# O4MEGA.net
KiCad netlist of a schematic drawn in EAGLE
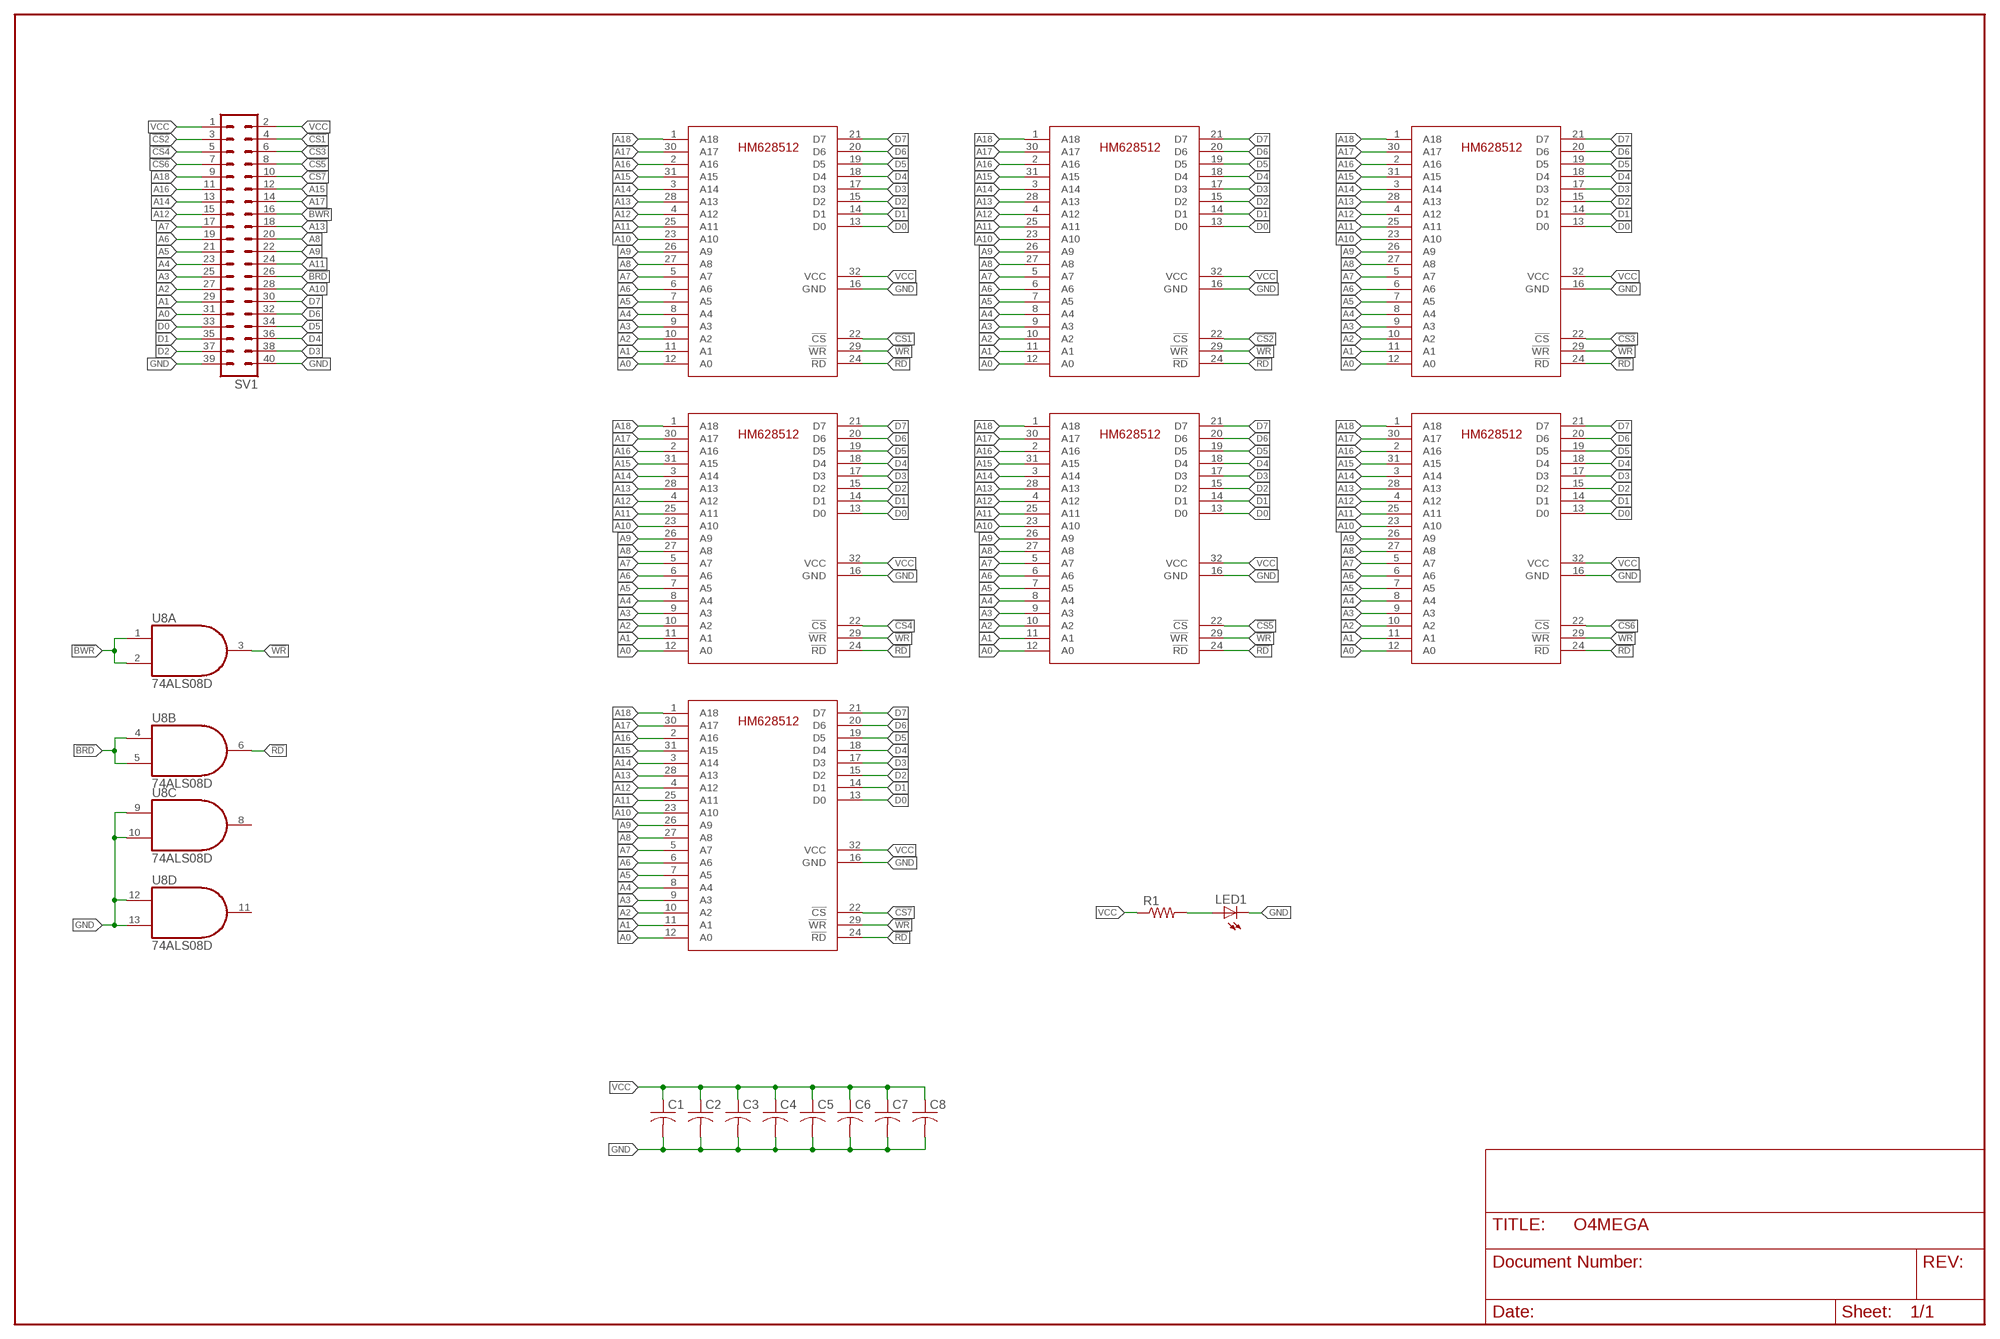
[diagram p0: schematic, sheet 1]

(export (version "E")
  (design (tool "Eeschema 10.0.6"))
  (components
    (comp (ref "C1")
      (value "C-USC0805K")
      (footprint "eagle-import:C0805K")
      (libsource (lib "eagle-import") (part "C-USC0805K"))
    )
    (comp (ref "C2")
      (value "C-USC0805K")
      (footprint "eagle-import:C0805K")
      (libsource (lib "eagle-import") (part "C-USC0805K"))
    )
    (comp (ref "C3")
      (value "C-USC0805K")
      (footprint "eagle-import:C0805K")
      (libsource (lib "eagle-import") (part "C-USC0805K"))
    )
    (comp (ref "C4")
      (value "C-USC0805K")
      (footprint "eagle-import:C0805K")
      (libsource (lib "eagle-import") (part "C-USC0805K"))
    )
    (comp (ref "C5")
      (value "C-USC0805K")
      (footprint "eagle-import:C0805K")
      (libsource (lib "eagle-import") (part "C-USC0805K"))
    )
    (comp (ref "C6")
      (value "C-USC0805K")
      (footprint "eagle-import:C0805K")
      (libsource (lib "eagle-import") (part "C-USC0805K"))
    )
    (comp (ref "C7")
      (value "C-USC0805K")
      (footprint "eagle-import:C0805K")
      (libsource (lib "eagle-import") (part "C-USC0805K"))
    )
    (comp (ref "C8")
      (value "C-USC0805K")
      (footprint "eagle-import:C0805K")
      (libsource (lib "eagle-import") (part "C-USC0805K"))
    )
    (comp (ref "LED1")
      (value "LEDCHIP-LED0805")
      (footprint "eagle-import:CHIP-LED0805")
      (libsource (lib "eagle-import") (part "LEDCHIP-LED0805"))
    )
    (comp (ref "R1")
      (value "R-US_M0805")
      (footprint "eagle-import:M0805")
      (libsource (lib "eagle-import") (part "R-US_M0805"))
    )
    (comp (ref "SV1")
      (value "MA20-2")
      (footprint "eagle-import:MA20-2")
      (libsource (lib "eagle-import") (part "MA20-2"))
    )
    (comp (ref "U1")
      (value "HM628512")
      (footprint "eagle-import:SOP32L")
      (libsource (lib "eagle-import") (part "HM628512"))
    )
    (comp (ref "U2")
      (value "HM628512")
      (footprint "eagle-import:SOP32L")
      (libsource (lib "eagle-import") (part "HM628512"))
    )
    (comp (ref "U3")
      (value "HM628512")
      (footprint "eagle-import:SOP32L")
      (libsource (lib "eagle-import") (part "HM628512"))
    )
    (comp (ref "U4")
      (value "HM628512")
      (footprint "eagle-import:SOP32L")
      (libsource (lib "eagle-import") (part "HM628512"))
    )
    (comp (ref "U5")
      (value "HM628512")
      (footprint "eagle-import:SOP32L")
      (libsource (lib "eagle-import") (part "HM628512"))
    )
    (comp (ref "U6")
      (value "HM628512")
      (footprint "eagle-import:SOP32L")
      (libsource (lib "eagle-import") (part "HM628512"))
    )
    (comp (ref "U7")
      (value "HM628512")
      (footprint "eagle-import:SOP32L")
      (libsource (lib "eagle-import") (part "HM628512"))
    )
    (comp (ref "U8")
      (value "74ALS08D")
      (footprint "eagle-import:SO14")
      (libsource (lib "eagle-import") (part "7408DALS"))
    )
  )
  (nets
    (net (code "1") (name "/~{BRD}") (class "Default")
      (node (ref "SV1") (pin "26") (pinfunction "26_26") (pintype "passive"))
      (node (ref "U8") (pin "4") (pinfunction "I0_4") (pintype "input"))
      (node (ref "U8") (pin "5") (pinfunction "I1_5") (pintype "input"))
    )
    (net (code "2") (name "/~{BWR}") (class "Default")
      (node (ref "SV1") (pin "16") (pinfunction "16_16") (pintype "passive"))
      (node (ref "U8") (pin "1") (pinfunction "I0_1") (pintype "input"))
      (node (ref "U8") (pin "2") (pinfunction "I1_2") (pintype "input"))
    )
    (net (code "3") (name "/~{CS1}") (class "Default")
      (node (ref "SV1") (pin "4") (pinfunction "4_4") (pintype "passive"))
      (node (ref "U1") (pin "22") (pinfunction "~{CS}_22") (pintype "bidirectional"))
    )
    (net (code "4") (name "/~{CS2}") (class "Default")
      (node (ref "SV1") (pin "3") (pinfunction "3_3") (pintype "passive"))
      (node (ref "U2") (pin "22") (pinfunction "~{CS}_22") (pintype "bidirectional"))
    )
    (net (code "5") (name "/~{CS3}") (class "Default")
      (node (ref "SV1") (pin "6") (pinfunction "6_6") (pintype "passive"))
      (node (ref "U3") (pin "22") (pinfunction "~{CS}_22") (pintype "bidirectional"))
    )
    (net (code "6") (name "/~{CS4}") (class "Default")
      (node (ref "SV1") (pin "5") (pinfunction "5_5") (pintype "passive"))
      (node (ref "U4") (pin "22") (pinfunction "~{CS}_22") (pintype "bidirectional"))
    )
    (net (code "7") (name "/~{CS5}") (class "Default")
      (node (ref "SV1") (pin "8") (pinfunction "8_8") (pintype "passive"))
      (node (ref "U5") (pin "22") (pinfunction "~{CS}_22") (pintype "bidirectional"))
    )
    (net (code "8") (name "/~{CS6}") (class "Default")
      (node (ref "SV1") (pin "7") (pinfunction "7_7") (pintype "passive"))
      (node (ref "U6") (pin "22") (pinfunction "~{CS}_22") (pintype "bidirectional"))
    )
    (net (code "9") (name "/~{CS7}") (class "Default")
      (node (ref "SV1") (pin "10") (pinfunction "10_10") (pintype "passive"))
      (node (ref "U7") (pin "22") (pinfunction "~{CS}_22") (pintype "bidirectional"))
    )
    (net (code "10") (name "/~{RD}") (class "Default")
      (node (ref "U1") (pin "24") (pinfunction "~{RD}_24") (pintype "bidirectional"))
      (node (ref "U2") (pin "24") (pinfunction "~{RD}_24") (pintype "bidirectional"))
      (node (ref "U3") (pin "24") (pinfunction "~{RD}_24") (pintype "bidirectional"))
      (node (ref "U4") (pin "24") (pinfunction "~{RD}_24") (pintype "bidirectional"))
      (node (ref "U5") (pin "24") (pinfunction "~{RD}_24") (pintype "bidirectional"))
      (node (ref "U6") (pin "24") (pinfunction "~{RD}_24") (pintype "bidirectional"))
      (node (ref "U7") (pin "24") (pinfunction "~{RD}_24") (pintype "bidirectional"))
      (node (ref "U8") (pin "6") (pinfunction "O_6") (pintype "output"))
    )
    (net (code "11") (name "/~{WR}") (class "Default")
      (node (ref "U1") (pin "29") (pinfunction "~{WR}_29") (pintype "bidirectional"))
      (node (ref "U2") (pin "29") (pinfunction "~{WR}_29") (pintype "bidirectional"))
      (node (ref "U3") (pin "29") (pinfunction "~{WR}_29") (pintype "bidirectional"))
      (node (ref "U4") (pin "29") (pinfunction "~{WR}_29") (pintype "bidirectional"))
      (node (ref "U5") (pin "29") (pinfunction "~{WR}_29") (pintype "bidirectional"))
      (node (ref "U6") (pin "29") (pinfunction "~{WR}_29") (pintype "bidirectional"))
      (node (ref "U7") (pin "29") (pinfunction "~{WR}_29") (pintype "bidirectional"))
      (node (ref "U8") (pin "3") (pinfunction "O_3") (pintype "output"))
    )
    (net (code "12") (name "A0") (class "Default")
      (node (ref "SV1") (pin "31") (pinfunction "31_31") (pintype "passive"))
      (node (ref "U1") (pin "12") (pinfunction "A0_12") (pintype "input"))
      (node (ref "U2") (pin "12") (pinfunction "A0_12") (pintype "input"))
      (node (ref "U3") (pin "12") (pinfunction "A0_12") (pintype "input"))
      (node (ref "U4") (pin "12") (pinfunction "A0_12") (pintype "input"))
      (node (ref "U5") (pin "12") (pinfunction "A0_12") (pintype "input"))
      (node (ref "U6") (pin "12") (pinfunction "A0_12") (pintype "input"))
      (node (ref "U7") (pin "12") (pinfunction "A0_12") (pintype "input"))
    )
    (net (code "13") (name "A1") (class "Default")
      (node (ref "SV1") (pin "29") (pinfunction "29_29") (pintype "passive"))
      (node (ref "U1") (pin "11") (pinfunction "A1_11") (pintype "input"))
      (node (ref "U2") (pin "11") (pinfunction "A1_11") (pintype "input"))
      (node (ref "U3") (pin "11") (pinfunction "A1_11") (pintype "input"))
      (node (ref "U4") (pin "11") (pinfunction "A1_11") (pintype "input"))
      (node (ref "U5") (pin "11") (pinfunction "A1_11") (pintype "input"))
      (node (ref "U6") (pin "11") (pinfunction "A1_11") (pintype "input"))
      (node (ref "U7") (pin "11") (pinfunction "A1_11") (pintype "input"))
    )
    (net (code "14") (name "A2") (class "Default")
      (node (ref "SV1") (pin "27") (pinfunction "27_27") (pintype "passive"))
      (node (ref "U1") (pin "10") (pinfunction "A2_10") (pintype "input"))
      (node (ref "U2") (pin "10") (pinfunction "A2_10") (pintype "input"))
      (node (ref "U3") (pin "10") (pinfunction "A2_10") (pintype "input"))
      (node (ref "U4") (pin "10") (pinfunction "A2_10") (pintype "input"))
      (node (ref "U5") (pin "10") (pinfunction "A2_10") (pintype "input"))
      (node (ref "U6") (pin "10") (pinfunction "A2_10") (pintype "input"))
      (node (ref "U7") (pin "10") (pinfunction "A2_10") (pintype "input"))
    )
    (net (code "15") (name "A3") (class "Default")
      (node (ref "SV1") (pin "25") (pinfunction "25_25") (pintype "passive"))
      (node (ref "U1") (pin "9") (pinfunction "A3_9") (pintype "input"))
      (node (ref "U2") (pin "9") (pinfunction "A3_9") (pintype "input"))
      (node (ref "U3") (pin "9") (pinfunction "A3_9") (pintype "input"))
      (node (ref "U4") (pin "9") (pinfunction "A3_9") (pintype "input"))
      (node (ref "U5") (pin "9") (pinfunction "A3_9") (pintype "input"))
      (node (ref "U6") (pin "9") (pinfunction "A3_9") (pintype "input"))
      (node (ref "U7") (pin "9") (pinfunction "A3_9") (pintype "input"))
    )
    (net (code "16") (name "A4") (class "Default")
      (node (ref "SV1") (pin "23") (pinfunction "23_23") (pintype "passive"))
      (node (ref "U1") (pin "8") (pinfunction "A4_8") (pintype "input"))
      (node (ref "U2") (pin "8") (pinfunction "A4_8") (pintype "input"))
      (node (ref "U3") (pin "8") (pinfunction "A4_8") (pintype "input"))
      (node (ref "U4") (pin "8") (pinfunction "A4_8") (pintype "input"))
      (node (ref "U5") (pin "8") (pinfunction "A4_8") (pintype "input"))
      (node (ref "U6") (pin "8") (pinfunction "A4_8") (pintype "input"))
      (node (ref "U7") (pin "8") (pinfunction "A4_8") (pintype "input"))
    )
    (net (code "17") (name "A5") (class "Default")
      (node (ref "SV1") (pin "21") (pinfunction "21_21") (pintype "passive"))
      (node (ref "U1") (pin "7") (pinfunction "A5_7") (pintype "input"))
      (node (ref "U2") (pin "7") (pinfunction "A5_7") (pintype "input"))
      (node (ref "U3") (pin "7") (pinfunction "A5_7") (pintype "input"))
      (node (ref "U4") (pin "7") (pinfunction "A5_7") (pintype "input"))
      (node (ref "U5") (pin "7") (pinfunction "A5_7") (pintype "input"))
      (node (ref "U6") (pin "7") (pinfunction "A5_7") (pintype "input"))
      (node (ref "U7") (pin "7") (pinfunction "A5_7") (pintype "input"))
    )
    (net (code "18") (name "A6") (class "Default")
      (node (ref "SV1") (pin "19") (pinfunction "19_19") (pintype "passive"))
      (node (ref "U1") (pin "6") (pinfunction "A6_6") (pintype "input"))
      (node (ref "U2") (pin "6") (pinfunction "A6_6") (pintype "input"))
      (node (ref "U3") (pin "6") (pinfunction "A6_6") (pintype "input"))
      (node (ref "U4") (pin "6") (pinfunction "A6_6") (pintype "input"))
      (node (ref "U5") (pin "6") (pinfunction "A6_6") (pintype "input"))
      (node (ref "U6") (pin "6") (pinfunction "A6_6") (pintype "input"))
      (node (ref "U7") (pin "6") (pinfunction "A6_6") (pintype "input"))
    )
    (net (code "19") (name "A7") (class "Default")
      (node (ref "SV1") (pin "17") (pinfunction "17_17") (pintype "passive"))
      (node (ref "U1") (pin "5") (pinfunction "A7_5") (pintype "input"))
      (node (ref "U2") (pin "5") (pinfunction "A7_5") (pintype "input"))
      (node (ref "U3") (pin "5") (pinfunction "A7_5") (pintype "input"))
      (node (ref "U4") (pin "5") (pinfunction "A7_5") (pintype "input"))
      (node (ref "U5") (pin "5") (pinfunction "A7_5") (pintype "input"))
      (node (ref "U6") (pin "5") (pinfunction "A7_5") (pintype "input"))
      (node (ref "U7") (pin "5") (pinfunction "A7_5") (pintype "input"))
    )
    (net (code "20") (name "A8") (class "Default")
      (node (ref "SV1") (pin "20") (pinfunction "20_20") (pintype "passive"))
      (node (ref "U1") (pin "27") (pinfunction "A8_27") (pintype "input"))
      (node (ref "U2") (pin "27") (pinfunction "A8_27") (pintype "input"))
      (node (ref "U3") (pin "27") (pinfunction "A8_27") (pintype "input"))
      (node (ref "U4") (pin "27") (pinfunction "A8_27") (pintype "input"))
      (node (ref "U5") (pin "27") (pinfunction "A8_27") (pintype "input"))
      (node (ref "U6") (pin "27") (pinfunction "A8_27") (pintype "input"))
      (node (ref "U7") (pin "27") (pinfunction "A8_27") (pintype "input"))
    )
    (net (code "21") (name "A9") (class "Default")
      (node (ref "SV1") (pin "22") (pinfunction "22_22") (pintype "passive"))
      (node (ref "U1") (pin "26") (pinfunction "A9_26") (pintype "input"))
      (node (ref "U2") (pin "26") (pinfunction "A9_26") (pintype "input"))
      (node (ref "U3") (pin "26") (pinfunction "A9_26") (pintype "input"))
      (node (ref "U4") (pin "26") (pinfunction "A9_26") (pintype "input"))
      (node (ref "U5") (pin "26") (pinfunction "A9_26") (pintype "input"))
      (node (ref "U6") (pin "26") (pinfunction "A9_26") (pintype "input"))
      (node (ref "U7") (pin "26") (pinfunction "A9_26") (pintype "input"))
    )
    (net (code "22") (name "A10") (class "Default")
      (node (ref "SV1") (pin "28") (pinfunction "28_28") (pintype "passive"))
      (node (ref "U1") (pin "23") (pinfunction "A10_23") (pintype "input"))
      (node (ref "U2") (pin "23") (pinfunction "A10_23") (pintype "input"))
      (node (ref "U3") (pin "23") (pinfunction "A10_23") (pintype "input"))
      (node (ref "U4") (pin "23") (pinfunction "A10_23") (pintype "input"))
      (node (ref "U5") (pin "23") (pinfunction "A10_23") (pintype "input"))
      (node (ref "U6") (pin "23") (pinfunction "A10_23") (pintype "input"))
      (node (ref "U7") (pin "23") (pinfunction "A10_23") (pintype "input"))
    )
    (net (code "23") (name "A11") (class "Default")
      (node (ref "SV1") (pin "24") (pinfunction "24_24") (pintype "passive"))
      (node (ref "U1") (pin "25") (pinfunction "A11_25") (pintype "input"))
      (node (ref "U2") (pin "25") (pinfunction "A11_25") (pintype "input"))
      (node (ref "U3") (pin "25") (pinfunction "A11_25") (pintype "input"))
      (node (ref "U4") (pin "25") (pinfunction "A11_25") (pintype "input"))
      (node (ref "U5") (pin "25") (pinfunction "A11_25") (pintype "input"))
      (node (ref "U6") (pin "25") (pinfunction "A11_25") (pintype "input"))
      (node (ref "U7") (pin "25") (pinfunction "A11_25") (pintype "input"))
    )
    (net (code "24") (name "A12") (class "Default")
      (node (ref "SV1") (pin "15") (pinfunction "15_15") (pintype "passive"))
      (node (ref "U1") (pin "4") (pinfunction "A12_4") (pintype "input"))
      (node (ref "U2") (pin "4") (pinfunction "A12_4") (pintype "input"))
      (node (ref "U3") (pin "4") (pinfunction "A12_4") (pintype "input"))
      (node (ref "U4") (pin "4") (pinfunction "A12_4") (pintype "input"))
      (node (ref "U5") (pin "4") (pinfunction "A12_4") (pintype "input"))
      (node (ref "U6") (pin "4") (pinfunction "A12_4") (pintype "input"))
      (node (ref "U7") (pin "4") (pinfunction "A12_4") (pintype "input"))
    )
    (net (code "25") (name "A13") (class "Default")
      (node (ref "SV1") (pin "18") (pinfunction "18_18") (pintype "passive"))
      (node (ref "U1") (pin "28") (pinfunction "A13_28") (pintype "input"))
      (node (ref "U2") (pin "28") (pinfunction "A13_28") (pintype "input"))
      (node (ref "U3") (pin "28") (pinfunction "A13_28") (pintype "input"))
      (node (ref "U4") (pin "28") (pinfunction "A13_28") (pintype "input"))
      (node (ref "U5") (pin "28") (pinfunction "A13_28") (pintype "input"))
      (node (ref "U6") (pin "28") (pinfunction "A13_28") (pintype "input"))
      (node (ref "U7") (pin "28") (pinfunction "A13_28") (pintype "input"))
    )
    (net (code "26") (name "A14") (class "Default")
      (node (ref "SV1") (pin "13") (pinfunction "13_13") (pintype "passive"))
      (node (ref "U1") (pin "3") (pinfunction "A14_3") (pintype "input"))
      (node (ref "U2") (pin "3") (pinfunction "A14_3") (pintype "input"))
      (node (ref "U3") (pin "3") (pinfunction "A14_3") (pintype "input"))
      (node (ref "U4") (pin "3") (pinfunction "A14_3") (pintype "input"))
      (node (ref "U5") (pin "3") (pinfunction "A14_3") (pintype "input"))
      (node (ref "U6") (pin "3") (pinfunction "A14_3") (pintype "input"))
      (node (ref "U7") (pin "3") (pinfunction "A14_3") (pintype "input"))
    )
    (net (code "27") (name "A15") (class "Default")
      (node (ref "SV1") (pin "12") (pinfunction "12_12") (pintype "passive"))
      (node (ref "U1") (pin "31") (pinfunction "A15_31") (pintype "input"))
      (node (ref "U2") (pin "31") (pinfunction "A15_31") (pintype "input"))
      (node (ref "U3") (pin "31") (pinfunction "A15_31") (pintype "input"))
      (node (ref "U4") (pin "31") (pinfunction "A15_31") (pintype "input"))
      (node (ref "U5") (pin "31") (pinfunction "A15_31") (pintype "input"))
      (node (ref "U6") (pin "31") (pinfunction "A15_31") (pintype "input"))
      (node (ref "U7") (pin "31") (pinfunction "A15_31") (pintype "input"))
    )
    (net (code "28") (name "A16") (class "Default")
      (node (ref "SV1") (pin "11") (pinfunction "11_11") (pintype "passive"))
      (node (ref "U1") (pin "2") (pinfunction "A16_2") (pintype "input"))
      (node (ref "U2") (pin "2") (pinfunction "A16_2") (pintype "input"))
      (node (ref "U3") (pin "2") (pinfunction "A16_2") (pintype "input"))
      (node (ref "U4") (pin "2") (pinfunction "A16_2") (pintype "input"))
      (node (ref "U5") (pin "2") (pinfunction "A16_2") (pintype "input"))
      (node (ref "U6") (pin "2") (pinfunction "A16_2") (pintype "input"))
      (node (ref "U7") (pin "2") (pinfunction "A16_2") (pintype "input"))
    )
    (net (code "29") (name "A17") (class "Default")
      (node (ref "SV1") (pin "14") (pinfunction "14_14") (pintype "passive"))
      (node (ref "U1") (pin "30") (pinfunction "A17_30") (pintype "input"))
      (node (ref "U2") (pin "30") (pinfunction "A17_30") (pintype "input"))
      (node (ref "U3") (pin "30") (pinfunction "A17_30") (pintype "input"))
      (node (ref "U4") (pin "30") (pinfunction "A17_30") (pintype "input"))
      (node (ref "U5") (pin "30") (pinfunction "A17_30") (pintype "input"))
      (node (ref "U6") (pin "30") (pinfunction "A17_30") (pintype "input"))
      (node (ref "U7") (pin "30") (pinfunction "A17_30") (pintype "input"))
    )
    (net (code "30") (name "A18") (class "Default")
      (node (ref "SV1") (pin "9") (pinfunction "9_9") (pintype "passive"))
      (node (ref "U1") (pin "1") (pinfunction "A18_1") (pintype "input"))
      (node (ref "U2") (pin "1") (pinfunction "A18_1") (pintype "input"))
      (node (ref "U3") (pin "1") (pinfunction "A18_1") (pintype "input"))
      (node (ref "U4") (pin "1") (pinfunction "A18_1") (pintype "input"))
      (node (ref "U5") (pin "1") (pinfunction "A18_1") (pintype "input"))
      (node (ref "U6") (pin "1") (pinfunction "A18_1") (pintype "input"))
      (node (ref "U7") (pin "1") (pinfunction "A18_1") (pintype "input"))
    )
    (net (code "31") (name "D0") (class "Default")
      (node (ref "SV1") (pin "33") (pinfunction "33_33") (pintype "passive"))
      (node (ref "U1") (pin "13") (pinfunction "D0_13") (pintype "bidirectional"))
      (node (ref "U2") (pin "13") (pinfunction "D0_13") (pintype "bidirectional"))
      (node (ref "U3") (pin "13") (pinfunction "D0_13") (pintype "bidirectional"))
      (node (ref "U4") (pin "13") (pinfunction "D0_13") (pintype "bidirectional"))
      (node (ref "U5") (pin "13") (pinfunction "D0_13") (pintype "bidirectional"))
      (node (ref "U6") (pin "13") (pinfunction "D0_13") (pintype "bidirectional"))
      (node (ref "U7") (pin "13") (pinfunction "D0_13") (pintype "bidirectional"))
    )
    (net (code "32") (name "D1") (class "Default")
      (node (ref "SV1") (pin "35") (pinfunction "35_35") (pintype "passive"))
      (node (ref "U1") (pin "14") (pinfunction "D1_14") (pintype "bidirectional"))
      (node (ref "U2") (pin "14") (pinfunction "D1_14") (pintype "bidirectional"))
      (node (ref "U3") (pin "14") (pinfunction "D1_14") (pintype "bidirectional"))
      (node (ref "U4") (pin "14") (pinfunction "D1_14") (pintype "bidirectional"))
      (node (ref "U5") (pin "14") (pinfunction "D1_14") (pintype "bidirectional"))
      (node (ref "U6") (pin "14") (pinfunction "D1_14") (pintype "bidirectional"))
      (node (ref "U7") (pin "14") (pinfunction "D1_14") (pintype "bidirectional"))
    )
    (net (code "33") (name "D2") (class "Default")
      (node (ref "SV1") (pin "37") (pinfunction "37_37") (pintype "passive"))
      (node (ref "U1") (pin "15") (pinfunction "D2_15") (pintype "bidirectional"))
      (node (ref "U2") (pin "15") (pinfunction "D2_15") (pintype "bidirectional"))
      (node (ref "U3") (pin "15") (pinfunction "D2_15") (pintype "bidirectional"))
      (node (ref "U4") (pin "15") (pinfunction "D2_15") (pintype "bidirectional"))
      (node (ref "U5") (pin "15") (pinfunction "D2_15") (pintype "bidirectional"))
      (node (ref "U6") (pin "15") (pinfunction "D2_15") (pintype "bidirectional"))
      (node (ref "U7") (pin "15") (pinfunction "D2_15") (pintype "bidirectional"))
    )
    (net (code "34") (name "D3") (class "Default")
      (node (ref "SV1") (pin "38") (pinfunction "38_38") (pintype "passive"))
      (node (ref "U1") (pin "17") (pinfunction "D3_17") (pintype "bidirectional"))
      (node (ref "U2") (pin "17") (pinfunction "D3_17") (pintype "bidirectional"))
      (node (ref "U3") (pin "17") (pinfunction "D3_17") (pintype "bidirectional"))
      (node (ref "U4") (pin "17") (pinfunction "D3_17") (pintype "bidirectional"))
      (node (ref "U5") (pin "17") (pinfunction "D3_17") (pintype "bidirectional"))
      (node (ref "U6") (pin "17") (pinfunction "D3_17") (pintype "bidirectional"))
      (node (ref "U7") (pin "17") (pinfunction "D3_17") (pintype "bidirectional"))
    )
    (net (code "35") (name "D4") (class "Default")
      (node (ref "SV1") (pin "36") (pinfunction "36_36") (pintype "passive"))
      (node (ref "U1") (pin "18") (pinfunction "D4_18") (pintype "bidirectional"))
      (node (ref "U2") (pin "18") (pinfunction "D4_18") (pintype "bidirectional"))
      (node (ref "U3") (pin "18") (pinfunction "D4_18") (pintype "bidirectional"))
      (node (ref "U4") (pin "18") (pinfunction "D4_18") (pintype "bidirectional"))
      (node (ref "U5") (pin "18") (pinfunction "D4_18") (pintype "bidirectional"))
      (node (ref "U6") (pin "18") (pinfunction "D4_18") (pintype "bidirectional"))
      (node (ref "U7") (pin "18") (pinfunction "D4_18") (pintype "bidirectional"))
    )
    (net (code "36") (name "D5") (class "Default")
      (node (ref "SV1") (pin "34") (pinfunction "34_34") (pintype "passive"))
      (node (ref "U1") (pin "19") (pinfunction "D5_19") (pintype "bidirectional"))
      (node (ref "U2") (pin "19") (pinfunction "D5_19") (pintype "bidirectional"))
      (node (ref "U3") (pin "19") (pinfunction "D5_19") (pintype "bidirectional"))
      (node (ref "U4") (pin "19") (pinfunction "D5_19") (pintype "bidirectional"))
      (node (ref "U5") (pin "19") (pinfunction "D5_19") (pintype "bidirectional"))
      (node (ref "U6") (pin "19") (pinfunction "D5_19") (pintype "bidirectional"))
      (node (ref "U7") (pin "19") (pinfunction "D5_19") (pintype "bidirectional"))
    )
    (net (code "37") (name "D6") (class "Default")
      (node (ref "SV1") (pin "32") (pinfunction "32_32") (pintype "passive"))
      (node (ref "U1") (pin "20") (pinfunction "D6_20") (pintype "bidirectional"))
      (node (ref "U2") (pin "20") (pinfunction "D6_20") (pintype "bidirectional"))
      (node (ref "U3") (pin "20") (pinfunction "D6_20") (pintype "bidirectional"))
      (node (ref "U4") (pin "20") (pinfunction "D6_20") (pintype "bidirectional"))
      (node (ref "U5") (pin "20") (pinfunction "D6_20") (pintype "bidirectional"))
      (node (ref "U6") (pin "20") (pinfunction "D6_20") (pintype "bidirectional"))
      (node (ref "U7") (pin "20") (pinfunction "D6_20") (pintype "bidirectional"))
    )
    (net (code "38") (name "D7") (class "Default")
      (node (ref "SV1") (pin "30") (pinfunction "30_30") (pintype "passive"))
      (node (ref "U1") (pin "21") (pinfunction "D7_21") (pintype "bidirectional"))
      (node (ref "U2") (pin "21") (pinfunction "D7_21") (pintype "bidirectional"))
      (node (ref "U3") (pin "21") (pinfunction "D7_21") (pintype "bidirectional"))
      (node (ref "U4") (pin "21") (pinfunction "D7_21") (pintype "bidirectional"))
      (node (ref "U5") (pin "21") (pinfunction "D7_21") (pintype "bidirectional"))
      (node (ref "U6") (pin "21") (pinfunction "D7_21") (pintype "bidirectional"))
      (node (ref "U7") (pin "21") (pinfunction "D7_21") (pintype "bidirectional"))
    )
    (net (code "39") (name "GND") (class "Default")
      (node (ref "C1") (pin "2") (pinfunction "2_2") (pintype "passive"))
      (node (ref "C2") (pin "2") (pinfunction "2_2") (pintype "passive"))
      (node (ref "C3") (pin "2") (pinfunction "2_2") (pintype "passive"))
      (node (ref "C4") (pin "2") (pinfunction "2_2") (pintype "passive"))
      (node (ref "C5") (pin "2") (pinfunction "2_2") (pintype "passive"))
      (node (ref "C6") (pin "2") (pinfunction "2_2") (pintype "passive"))
      (node (ref "C7") (pin "2") (pinfunction "2_2") (pintype "passive"))
      (node (ref "C8") (pin "2") (pinfunction "2_2") (pintype "passive"))
      (node (ref "LED1") (pin "C") (pinfunction "C_C") (pintype "passive"))
      (node (ref "SV1") (pin "39") (pinfunction "39_39") (pintype "passive"))
      (node (ref "SV1") (pin "40") (pinfunction "40_40") (pintype "passive"))
      (node (ref "U1") (pin "16") (pinfunction "GND_16") (pintype "bidirectional"))
      (node (ref "U2") (pin "16") (pinfunction "GND_16") (pintype "bidirectional"))
      (node (ref "U3") (pin "16") (pinfunction "GND_16") (pintype "bidirectional"))
      (node (ref "U4") (pin "16") (pinfunction "GND_16") (pintype "bidirectional"))
      (node (ref "U5") (pin "16") (pinfunction "GND_16") (pintype "bidirectional"))
      (node (ref "U6") (pin "16") (pinfunction "GND_16") (pintype "bidirectional"))
      (node (ref "U7") (pin "16") (pinfunction "GND_16") (pintype "bidirectional"))
      (node (ref "U8") (pin "10") (pinfunction "I1_10") (pintype "input"))
      (node (ref "U8") (pin "12") (pinfunction "I0_12") (pintype "input"))
      (node (ref "U8") (pin "13") (pinfunction "I1_13") (pintype "input"))
      (node (ref "U8") (pin "9") (pinfunction "I0_9") (pintype "input"))
    )
    (net (code "40") (name "Net-(LED1-PadA)") (class "Default")
      (node (ref "LED1") (pin "A") (pinfunction "A_A") (pintype "passive"))
      (node (ref "R1") (pin "2") (pinfunction "2_2") (pintype "passive"))
    )
    (net (code "41") (name "VCC") (class "Default")
      (node (ref "C1") (pin "1") (pinfunction "1_1") (pintype "passive"))
      (node (ref "C2") (pin "1") (pinfunction "1_1") (pintype "passive"))
      (node (ref "C3") (pin "1") (pinfunction "1_1") (pintype "passive"))
      (node (ref "C4") (pin "1") (pinfunction "1_1") (pintype "passive"))
      (node (ref "C5") (pin "1") (pinfunction "1_1") (pintype "passive"))
      (node (ref "C6") (pin "1") (pinfunction "1_1") (pintype "passive"))
      (node (ref "C7") (pin "1") (pinfunction "1_1") (pintype "passive"))
      (node (ref "C8") (pin "1") (pinfunction "1_1") (pintype "passive"))
      (node (ref "R1") (pin "1") (pinfunction "1_1") (pintype "passive"))
      (node (ref "SV1") (pin "1") (pinfunction "1_1") (pintype "passive"))
      (node (ref "SV1") (pin "2") (pinfunction "2_2") (pintype "passive"))
      (node (ref "U1") (pin "32") (pinfunction "VCC_32") (pintype "bidirectional"))
      (node (ref "U2") (pin "32") (pinfunction "VCC_32") (pintype "bidirectional"))
      (node (ref "U3") (pin "32") (pinfunction "VCC_32") (pintype "bidirectional"))
      (node (ref "U4") (pin "32") (pinfunction "VCC_32") (pintype "bidirectional"))
      (node (ref "U5") (pin "32") (pinfunction "VCC_32") (pintype "bidirectional"))
      (node (ref "U6") (pin "32") (pinfunction "VCC_32") (pintype "bidirectional"))
      (node (ref "U7") (pin "32") (pinfunction "VCC_32") (pintype "bidirectional"))
    )
    (net (code "42") (name "unconnected-(U8C-O-Pad8)") (class "Default")
      (node (ref "U8") (pin "8") (pinfunction "O_8") (pintype "output"))
    )
    (net (code "43") (name "unconnected-(U8D-O-Pad11)") (class "Default")
      (node (ref "U8") (pin "11") (pinfunction "O_11") (pintype "output"))
    )
  )
)
